# GPIO_Adapter.net
KiCad netlist of a schematic drawn in EAGLE
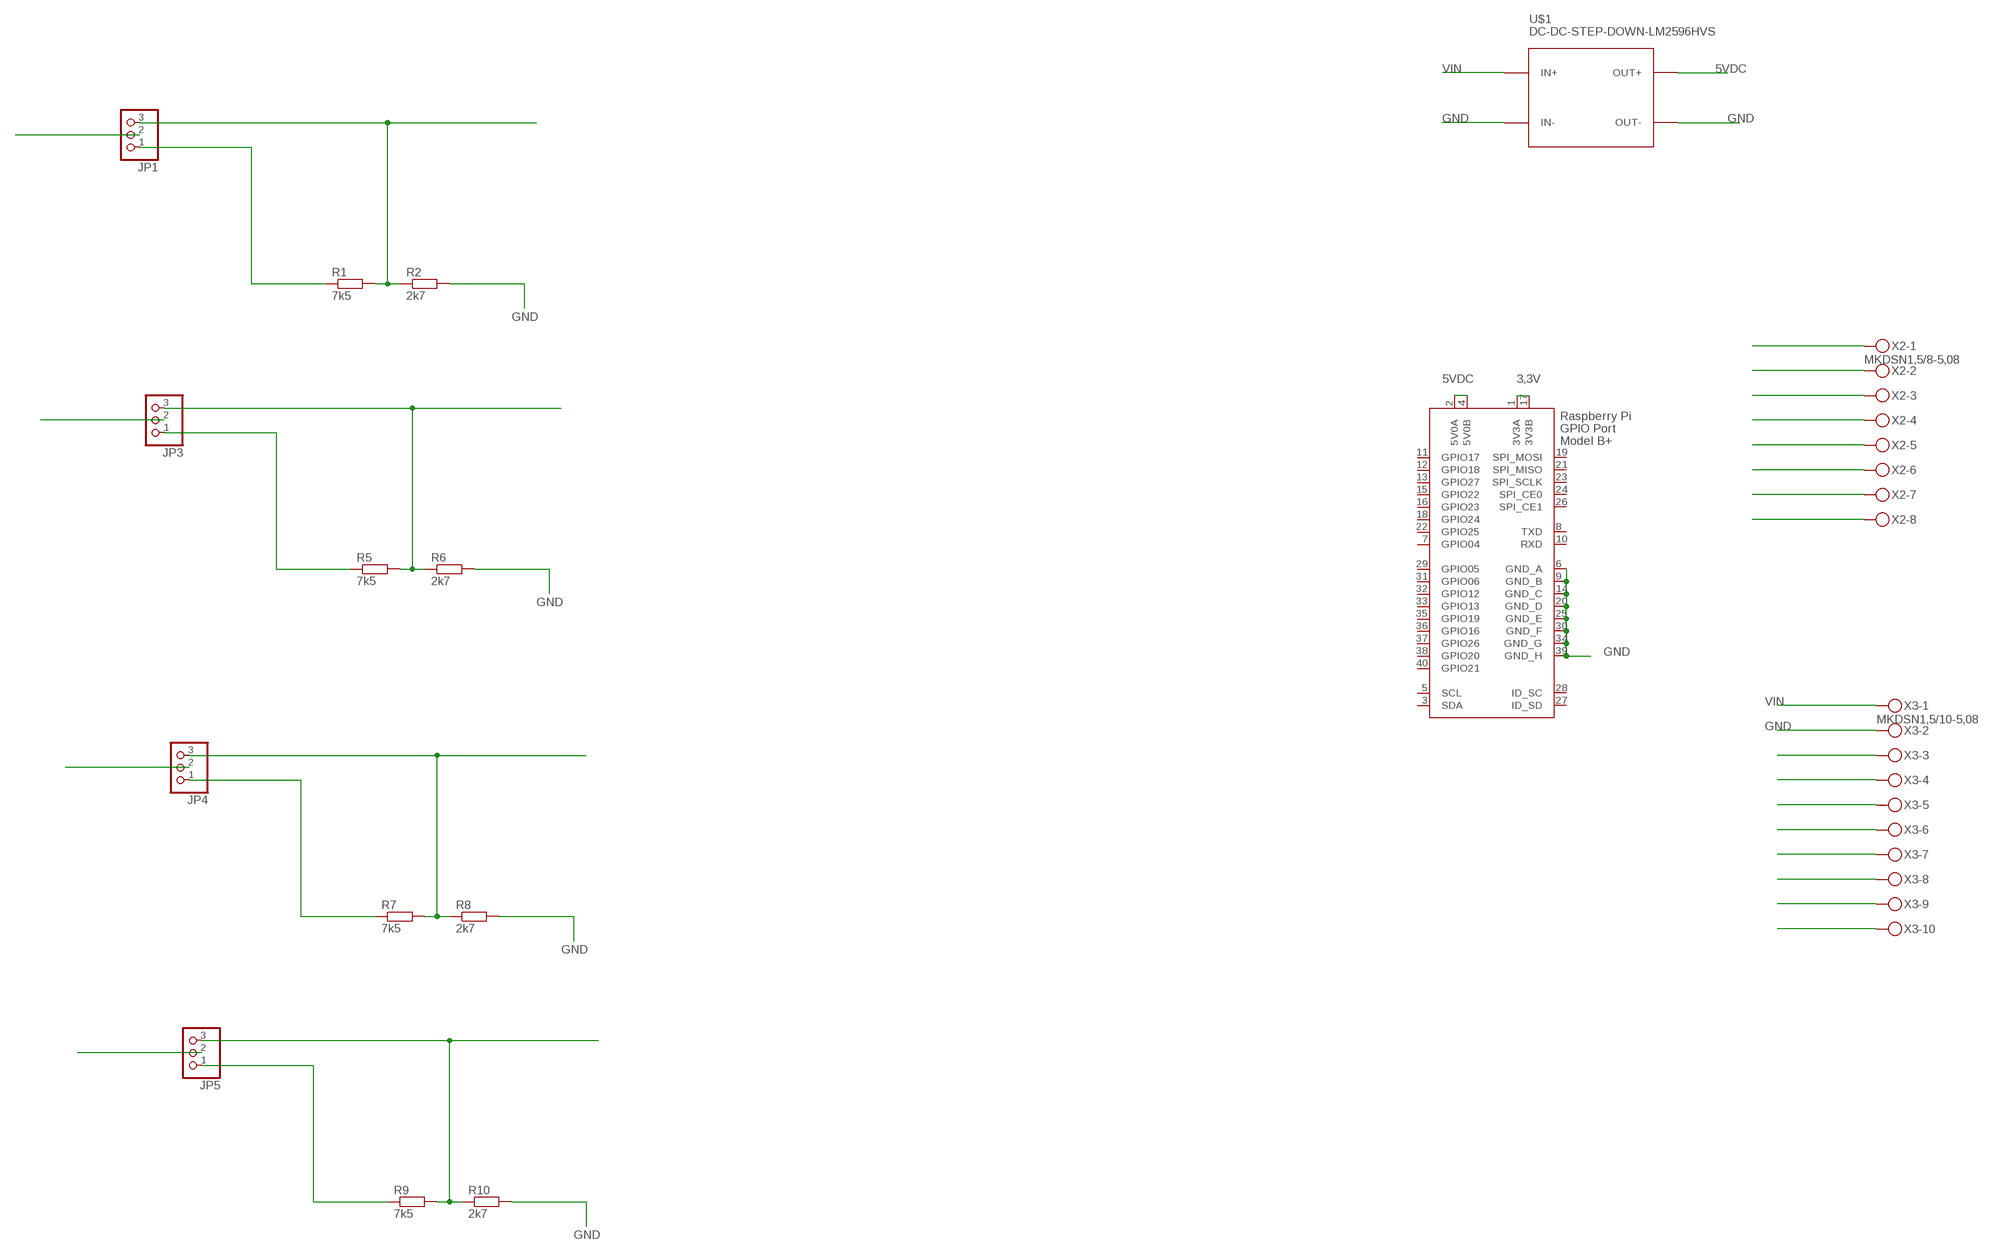
[diagram p0: schematic, sheet 1, part 1 of 3]
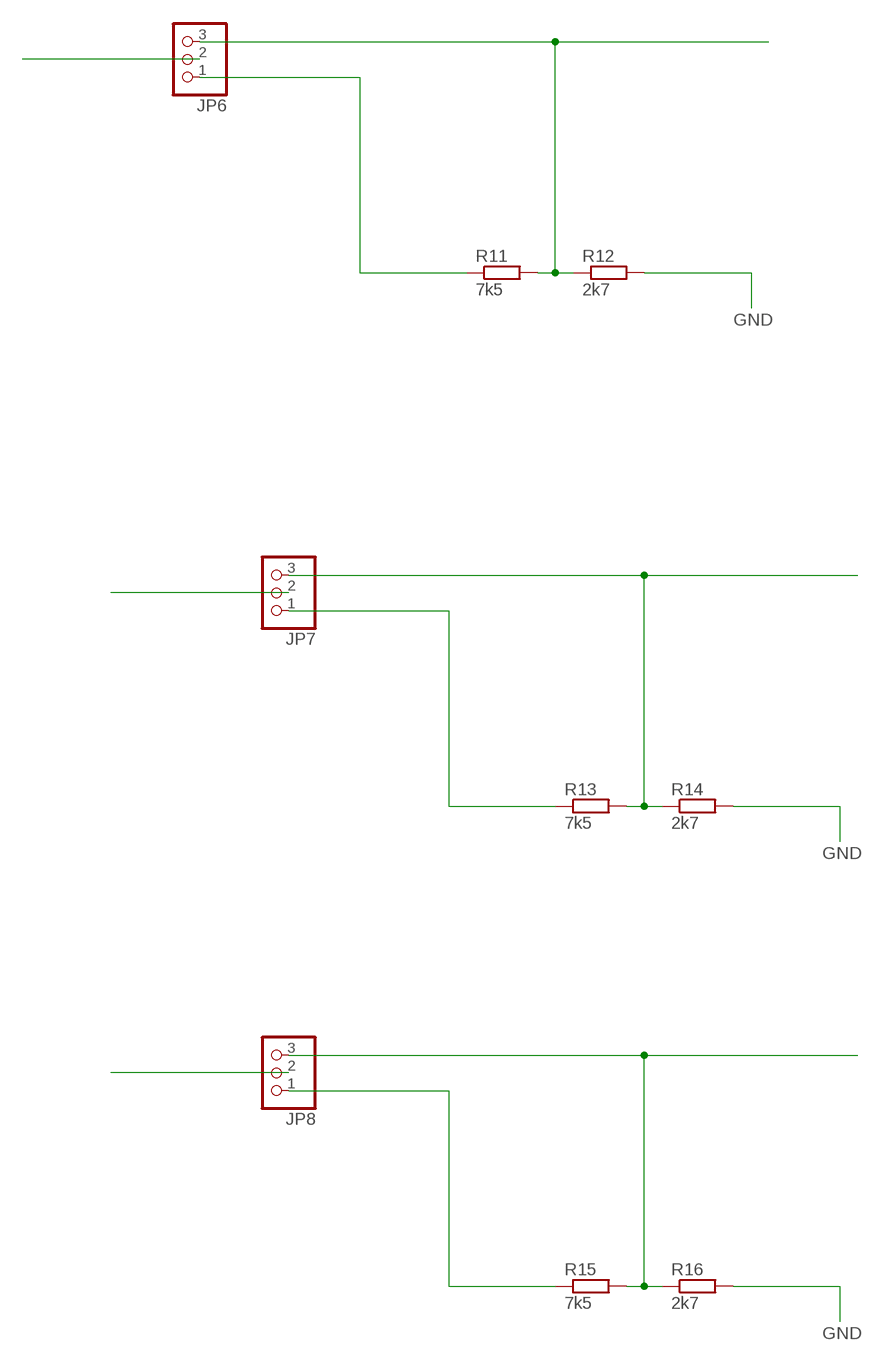
[diagram p1: schematic, sheet 1, part 2 of 3]
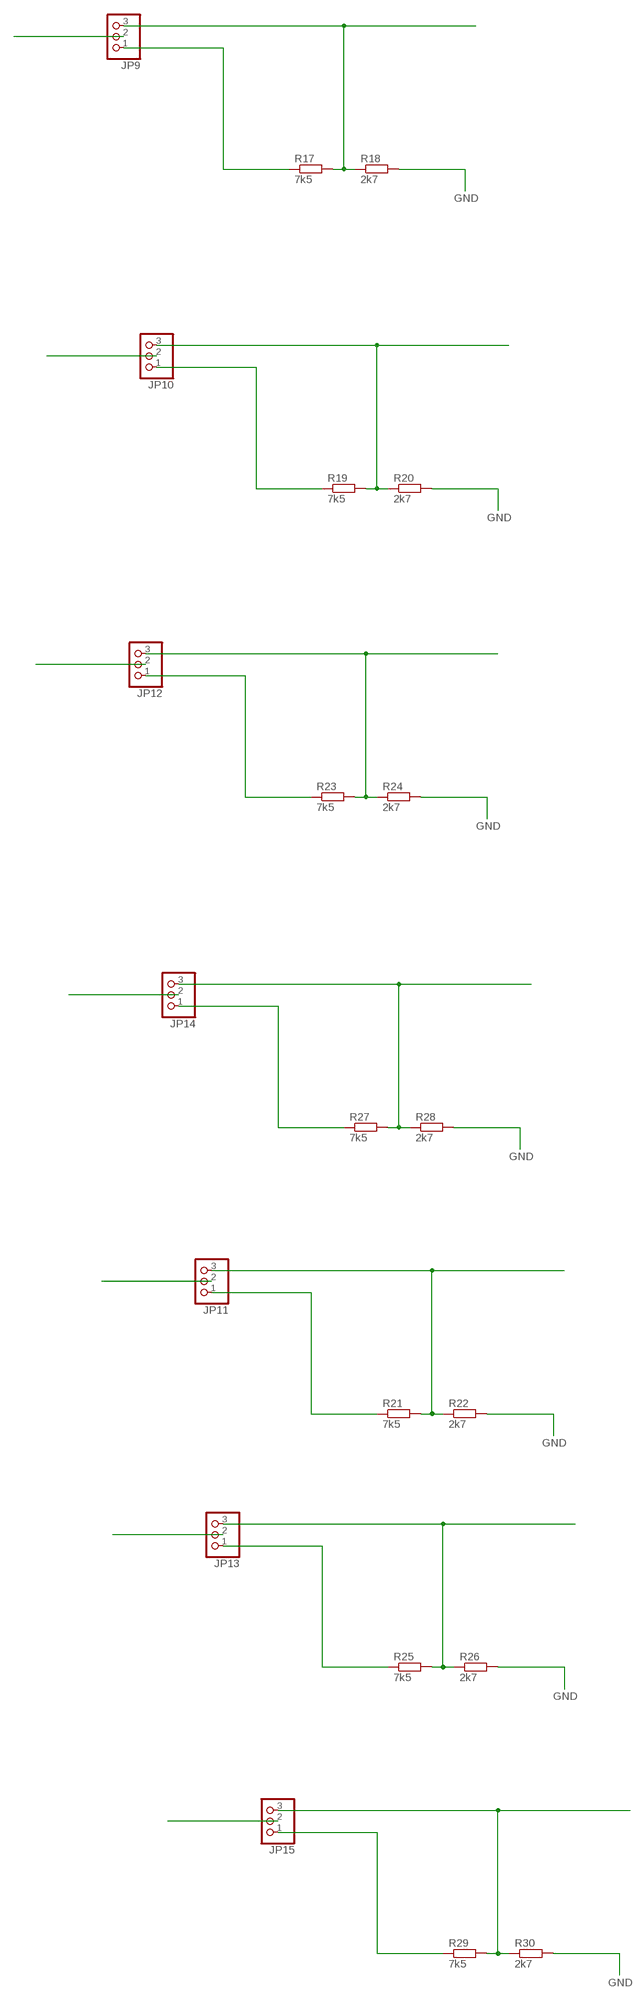
[diagram p2: schematic, sheet 1, part 3 of 3]

(export (version "E")
  (design (tool "Eeschema 10.0.6"))
  (components
    (comp (ref "JP1")
      (value "PINHD-1X3")
      (footprint "eagle-import:1X03")
      (libsource (lib "eagle-import") (part "PINHD-1X3"))
    )
    (comp (ref "JP3")
      (value "PINHD-1X3")
      (footprint "eagle-import:1X03")
      (libsource (lib "eagle-import") (part "PINHD-1X3"))
    )
    (comp (ref "JP4")
      (value "PINHD-1X3")
      (footprint "eagle-import:1X03")
      (libsource (lib "eagle-import") (part "PINHD-1X3"))
    )
    (comp (ref "JP5")
      (value "PINHD-1X3")
      (footprint "eagle-import:1X03")
      (libsource (lib "eagle-import") (part "PINHD-1X3"))
    )
    (comp (ref "JP6")
      (value "PINHD-1X3")
      (footprint "eagle-import:1X03")
      (libsource (lib "eagle-import") (part "PINHD-1X3"))
    )
    (comp (ref "JP7")
      (value "PINHD-1X3")
      (footprint "eagle-import:1X03")
      (libsource (lib "eagle-import") (part "PINHD-1X3"))
    )
    (comp (ref "JP8")
      (value "PINHD-1X3")
      (footprint "eagle-import:1X03")
      (libsource (lib "eagle-import") (part "PINHD-1X3"))
    )
    (comp (ref "JP9")
      (value "PINHD-1X3")
      (footprint "eagle-import:1X03")
      (libsource (lib "eagle-import") (part "PINHD-1X3"))
    )
    (comp (ref "JP10")
      (value "PINHD-1X3")
      (footprint "eagle-import:1X03")
      (libsource (lib "eagle-import") (part "PINHD-1X3"))
    )
    (comp (ref "JP11")
      (value "PINHD-1X3")
      (footprint "eagle-import:1X03")
      (libsource (lib "eagle-import") (part "PINHD-1X3"))
    )
    (comp (ref "JP12")
      (value "PINHD-1X3")
      (footprint "eagle-import:1X03")
      (libsource (lib "eagle-import") (part "PINHD-1X3"))
    )
    (comp (ref "JP13")
      (value "PINHD-1X3")
      (footprint "eagle-import:1X03")
      (libsource (lib "eagle-import") (part "PINHD-1X3"))
    )
    (comp (ref "JP14")
      (value "PINHD-1X3")
      (footprint "eagle-import:1X03")
      (libsource (lib "eagle-import") (part "PINHD-1X3"))
    )
    (comp (ref "JP15")
      (value "PINHD-1X3")
      (footprint "eagle-import:1X03")
      (libsource (lib "eagle-import") (part "PINHD-1X3"))
    )
    (comp (ref "R1")
      (value "7k5")
      (footprint "eagle-import:R0805")
      (libsource (lib "eagle-import") (part "R-EU_R0805"))
    )
    (comp (ref "R2")
      (value "2k7")
      (footprint "eagle-import:R0805")
      (libsource (lib "eagle-import") (part "R-EU_R0805"))
    )
    (comp (ref "R5")
      (value "7k5")
      (footprint "eagle-import:R0805")
      (libsource (lib "eagle-import") (part "R-EU_R0805"))
    )
    (comp (ref "R6")
      (value "2k7")
      (footprint "eagle-import:R0805")
      (libsource (lib "eagle-import") (part "R-EU_R0805"))
    )
    (comp (ref "R7")
      (value "7k5")
      (footprint "eagle-import:R0805")
      (libsource (lib "eagle-import") (part "R-EU_R0805"))
    )
    (comp (ref "R8")
      (value "2k7")
      (footprint "eagle-import:R0805")
      (libsource (lib "eagle-import") (part "R-EU_R0805"))
    )
    (comp (ref "R9")
      (value "7k5")
      (footprint "eagle-import:R0805")
      (libsource (lib "eagle-import") (part "R-EU_R0805"))
    )
    (comp (ref "R10")
      (value "2k7")
      (footprint "eagle-import:R0805")
      (libsource (lib "eagle-import") (part "R-EU_R0805"))
    )
    (comp (ref "R11")
      (value "7k5")
      (footprint "eagle-import:R0805")
      (libsource (lib "eagle-import") (part "R-EU_R0805"))
    )
    (comp (ref "R12")
      (value "2k7")
      (footprint "eagle-import:R0805")
      (libsource (lib "eagle-import") (part "R-EU_R0805"))
    )
    (comp (ref "R13")
      (value "7k5")
      (footprint "eagle-import:R0805")
      (libsource (lib "eagle-import") (part "R-EU_R0805"))
    )
    (comp (ref "R14")
      (value "2k7")
      (footprint "eagle-import:R0805")
      (libsource (lib "eagle-import") (part "R-EU_R0805"))
    )
    (comp (ref "R15")
      (value "7k5")
      (footprint "eagle-import:R0805")
      (libsource (lib "eagle-import") (part "R-EU_R0805"))
    )
    (comp (ref "R16")
      (value "2k7")
      (footprint "eagle-import:R0805")
      (libsource (lib "eagle-import") (part "R-EU_R0805"))
    )
    (comp (ref "R17")
      (value "7k5")
      (footprint "eagle-import:R0805")
      (libsource (lib "eagle-import") (part "R-EU_R0805"))
    )
    (comp (ref "R18")
      (value "2k7")
      (footprint "eagle-import:R0805")
      (libsource (lib "eagle-import") (part "R-EU_R0805"))
    )
    (comp (ref "R19")
      (value "7k5")
      (footprint "eagle-import:R0805")
      (libsource (lib "eagle-import") (part "R-EU_R0805"))
    )
    (comp (ref "R20")
      (value "2k7")
      (footprint "eagle-import:R0805")
      (libsource (lib "eagle-import") (part "R-EU_R0805"))
    )
    (comp (ref "R21")
      (value "7k5")
      (footprint "eagle-import:R0805")
      (libsource (lib "eagle-import") (part "R-EU_R0805"))
    )
    (comp (ref "R22")
      (value "2k7")
      (footprint "eagle-import:R0805")
      (libsource (lib "eagle-import") (part "R-EU_R0805"))
    )
    (comp (ref "R23")
      (value "7k5")
      (footprint "eagle-import:R0805")
      (libsource (lib "eagle-import") (part "R-EU_R0805"))
    )
    (comp (ref "R24")
      (value "2k7")
      (footprint "eagle-import:R0805")
      (libsource (lib "eagle-import") (part "R-EU_R0805"))
    )
    (comp (ref "R25")
      (value "7k5")
      (footprint "eagle-import:R0805")
      (libsource (lib "eagle-import") (part "R-EU_R0805"))
    )
    (comp (ref "R26")
      (value "2k7")
      (footprint "eagle-import:R0805")
      (libsource (lib "eagle-import") (part "R-EU_R0805"))
    )
    (comp (ref "R27")
      (value "7k5")
      (footprint "eagle-import:R0805")
      (libsource (lib "eagle-import") (part "R-EU_R0805"))
    )
    (comp (ref "R28")
      (value "2k7")
      (footprint "eagle-import:R0805")
      (libsource (lib "eagle-import") (part "R-EU_R0805"))
    )
    (comp (ref "R29")
      (value "7k5")
      (footprint "eagle-import:R0805")
      (libsource (lib "eagle-import") (part "R-EU_R0805"))
    )
    (comp (ref "R30")
      (value "2k7")
      (footprint "eagle-import:R0805")
      (libsource (lib "eagle-import") (part "R-EU_R0805"))
    )
    (comp (ref "U$1")
      (value "DC-DC-STEP-DOWN-LM2596HVS")
      (footprint "eagle-import:DC-DC-STEP-DOWN-LM2596HVS")
      (libsource (lib "eagle-import") (part "DC-DC-STEP-DOWN-LM2596HVS"))
    )
    (comp (ref "X1")
      (value "RASPI_BOARD_B+#_F")
      (footprint "eagle-import:RASPI_BOARD_B+_FULL")
      (libsource (lib "eagle-import") (part "RASPI_BOARD_B+#_F"))
    )
    (comp (ref "X2")
      (value "MKDSN1,5/8-5,08")
      (footprint "eagle-import:MKDSN1,5_8-5,08")
      (libsource (lib "eagle-import") (part "MKDSN1,5/8-5,08"))
    )
    (comp (ref "X3")
      (value "MKDSN1,5/10-5,08")
      (footprint "eagle-import:MKDSN1,5_10-5,08")
      (libsource (lib "eagle-import") (part "MKDSN1,5/10-5,08"))
    )
  )
  (nets
    (net (code "1") (name "/3,3V") (class "Default")
      (node (ref "X1") (pin "1") (pinfunction "3V3A_1") (pintype "power_in"))
      (node (ref "X1") (pin "17") (pinfunction "3V3B_17") (pintype "power_in"))
    )
    (net (code "2") (name "/5VDC") (class "Default")
      (node (ref "U$1") (pin "OUT+") (pinfunction "OUT+_OUT+") (pintype "bidirectional"))
      (node (ref "X1") (pin "2") (pinfunction "5V0A_2") (pintype "power_in"))
      (node (ref "X1") (pin "4") (pinfunction "5V0B_4") (pintype "power_in"))
    )
    (net (code "3") (name "/GND") (class "Default")
      (node (ref "R10") (pin "2") (pinfunction "2_2") (pintype "passive"))
      (node (ref "R12") (pin "2") (pinfunction "2_2") (pintype "passive"))
      (node (ref "R14") (pin "2") (pinfunction "2_2") (pintype "passive"))
      (node (ref "R16") (pin "2") (pinfunction "2_2") (pintype "passive"))
      (node (ref "R18") (pin "2") (pinfunction "2_2") (pintype "passive"))
      (node (ref "R2") (pin "2") (pinfunction "2_2") (pintype "passive"))
      (node (ref "R20") (pin "2") (pinfunction "2_2") (pintype "passive"))
      (node (ref "R22") (pin "2") (pinfunction "2_2") (pintype "passive"))
      (node (ref "R24") (pin "2") (pinfunction "2_2") (pintype "passive"))
      (node (ref "R26") (pin "2") (pinfunction "2_2") (pintype "passive"))
      (node (ref "R28") (pin "2") (pinfunction "2_2") (pintype "passive"))
      (node (ref "R30") (pin "2") (pinfunction "2_2") (pintype "passive"))
      (node (ref "R6") (pin "2") (pinfunction "2_2") (pintype "passive"))
      (node (ref "R8") (pin "2") (pinfunction "2_2") (pintype "passive"))
      (node (ref "U$1") (pin "IN-") (pinfunction "IN-_IN-") (pintype "bidirectional"))
      (node (ref "U$1") (pin "OUT-") (pinfunction "OUT-_OUT-") (pintype "bidirectional"))
      (node (ref "X1") (pin "14") (pinfunction "GND_C_14") (pintype "power_in"))
      (node (ref "X1") (pin "20") (pinfunction "GND_D_20") (pintype "power_in"))
      (node (ref "X1") (pin "25") (pinfunction "GND_E_25") (pintype "power_in"))
      (node (ref "X1") (pin "30") (pinfunction "GND_F_30") (pintype "power_in"))
      (node (ref "X1") (pin "34") (pinfunction "GND_G_34") (pintype "power_in"))
      (node (ref "X1") (pin "39") (pinfunction "GND_H_39") (pintype "power_in"))
      (node (ref "X1") (pin "6") (pinfunction "GND_A_6") (pintype "power_in"))
      (node (ref "X1") (pin "9") (pinfunction "GND_B_9") (pintype "power_in"))
      (node (ref "X3") (pin "2") (pinfunction "KL_2") (pintype "passive"))
    )
    (net (code "4") (name "/VIN") (class "Default")
      (node (ref "U$1") (pin "IN+") (pinfunction "IN+_IN+") (pintype "bidirectional"))
      (node (ref "X3") (pin "1") (pinfunction "KL_1") (pintype "passive"))
    )
    (net (code "5") (name "Net-(JP1-Pad1)") (class "Default")
      (node (ref "JP1") (pin "1") (pinfunction "1_1") (pintype "passive"))
      (node (ref "R1") (pin "1") (pinfunction "1_1") (pintype "passive"))
    )
    (net (code "6") (name "Net-(JP1-Pad3)") (class "Default")
      (node (ref "JP1") (pin "3") (pinfunction "3_3") (pintype "passive"))
      (node (ref "R1") (pin "2") (pinfunction "2_2") (pintype "passive"))
      (node (ref "R2") (pin "1") (pinfunction "1_1") (pintype "passive"))
    )
    (net (code "7") (name "Net-(JP3-Pad1)") (class "Default")
      (node (ref "JP3") (pin "1") (pinfunction "1_1") (pintype "passive"))
      (node (ref "R5") (pin "1") (pinfunction "1_1") (pintype "passive"))
    )
    (net (code "8") (name "Net-(JP3-Pad3)") (class "Default")
      (node (ref "JP3") (pin "3") (pinfunction "3_3") (pintype "passive"))
      (node (ref "R5") (pin "2") (pinfunction "2_2") (pintype "passive"))
      (node (ref "R6") (pin "1") (pinfunction "1_1") (pintype "passive"))
    )
    (net (code "9") (name "Net-(JP4-Pad1)") (class "Default")
      (node (ref "JP4") (pin "1") (pinfunction "1_1") (pintype "passive"))
      (node (ref "R7") (pin "1") (pinfunction "1_1") (pintype "passive"))
    )
    (net (code "10") (name "Net-(JP4-Pad3)") (class "Default")
      (node (ref "JP4") (pin "3") (pinfunction "3_3") (pintype "passive"))
      (node (ref "R7") (pin "2") (pinfunction "2_2") (pintype "passive"))
      (node (ref "R8") (pin "1") (pinfunction "1_1") (pintype "passive"))
    )
    (net (code "11") (name "Net-(JP5-Pad1)") (class "Default")
      (node (ref "JP5") (pin "1") (pinfunction "1_1") (pintype "passive"))
      (node (ref "R9") (pin "1") (pinfunction "1_1") (pintype "passive"))
    )
    (net (code "12") (name "Net-(JP5-Pad3)") (class "Default")
      (node (ref "JP5") (pin "3") (pinfunction "3_3") (pintype "passive"))
      (node (ref "R10") (pin "1") (pinfunction "1_1") (pintype "passive"))
      (node (ref "R9") (pin "2") (pinfunction "2_2") (pintype "passive"))
    )
    (net (code "13") (name "Net-(JP6-Pad1)") (class "Default")
      (node (ref "JP6") (pin "1") (pinfunction "1_1") (pintype "passive"))
      (node (ref "R11") (pin "1") (pinfunction "1_1") (pintype "passive"))
    )
    (net (code "14") (name "Net-(JP6-Pad3)") (class "Default")
      (node (ref "JP6") (pin "3") (pinfunction "3_3") (pintype "passive"))
      (node (ref "R11") (pin "2") (pinfunction "2_2") (pintype "passive"))
      (node (ref "R12") (pin "1") (pinfunction "1_1") (pintype "passive"))
    )
    (net (code "15") (name "Net-(JP7-Pad1)") (class "Default")
      (node (ref "JP7") (pin "1") (pinfunction "1_1") (pintype "passive"))
      (node (ref "R13") (pin "1") (pinfunction "1_1") (pintype "passive"))
    )
    (net (code "16") (name "Net-(JP7-Pad3)") (class "Default")
      (node (ref "JP7") (pin "3") (pinfunction "3_3") (pintype "passive"))
      (node (ref "R13") (pin "2") (pinfunction "2_2") (pintype "passive"))
      (node (ref "R14") (pin "1") (pinfunction "1_1") (pintype "passive"))
    )
    (net (code "17") (name "Net-(JP8-Pad1)") (class "Default")
      (node (ref "JP8") (pin "1") (pinfunction "1_1") (pintype "passive"))
      (node (ref "R15") (pin "1") (pinfunction "1_1") (pintype "passive"))
    )
    (net (code "18") (name "Net-(JP8-Pad3)") (class "Default")
      (node (ref "JP8") (pin "3") (pinfunction "3_3") (pintype "passive"))
      (node (ref "R15") (pin "2") (pinfunction "2_2") (pintype "passive"))
      (node (ref "R16") (pin "1") (pinfunction "1_1") (pintype "passive"))
    )
    (net (code "19") (name "Net-(JP9-Pad1)") (class "Default")
      (node (ref "JP9") (pin "1") (pinfunction "1_1") (pintype "passive"))
      (node (ref "R17") (pin "1") (pinfunction "1_1") (pintype "passive"))
    )
    (net (code "20") (name "Net-(JP9-Pad3)") (class "Default")
      (node (ref "JP9") (pin "3") (pinfunction "3_3") (pintype "passive"))
      (node (ref "R17") (pin "2") (pinfunction "2_2") (pintype "passive"))
      (node (ref "R18") (pin "1") (pinfunction "1_1") (pintype "passive"))
    )
    (net (code "21") (name "Net-(JP10-Pad1)") (class "Default")
      (node (ref "JP10") (pin "1") (pinfunction "1_1") (pintype "passive"))
      (node (ref "R19") (pin "1") (pinfunction "1_1") (pintype "passive"))
    )
    (net (code "22") (name "Net-(JP10-Pad3)") (class "Default")
      (node (ref "JP10") (pin "3") (pinfunction "3_3") (pintype "passive"))
      (node (ref "R19") (pin "2") (pinfunction "2_2") (pintype "passive"))
      (node (ref "R20") (pin "1") (pinfunction "1_1") (pintype "passive"))
    )
    (net (code "23") (name "Net-(JP11-Pad1)") (class "Default")
      (node (ref "JP11") (pin "1") (pinfunction "1_1") (pintype "passive"))
      (node (ref "R21") (pin "1") (pinfunction "1_1") (pintype "passive"))
    )
    (net (code "24") (name "Net-(JP11-Pad3)") (class "Default")
      (node (ref "JP11") (pin "3") (pinfunction "3_3") (pintype "passive"))
      (node (ref "R21") (pin "2") (pinfunction "2_2") (pintype "passive"))
      (node (ref "R22") (pin "1") (pinfunction "1_1") (pintype "passive"))
    )
    (net (code "25") (name "Net-(JP12-Pad1)") (class "Default")
      (node (ref "JP12") (pin "1") (pinfunction "1_1") (pintype "passive"))
      (node (ref "R23") (pin "1") (pinfunction "1_1") (pintype "passive"))
    )
    (net (code "26") (name "Net-(JP12-Pad3)") (class "Default")
      (node (ref "JP12") (pin "3") (pinfunction "3_3") (pintype "passive"))
      (node (ref "R23") (pin "2") (pinfunction "2_2") (pintype "passive"))
      (node (ref "R24") (pin "1") (pinfunction "1_1") (pintype "passive"))
    )
    (net (code "27") (name "Net-(JP13-Pad1)") (class "Default")
      (node (ref "JP13") (pin "1") (pinfunction "1_1") (pintype "passive"))
      (node (ref "R25") (pin "1") (pinfunction "1_1") (pintype "passive"))
    )
    (net (code "28") (name "Net-(JP13-Pad3)") (class "Default")
      (node (ref "JP13") (pin "3") (pinfunction "3_3") (pintype "passive"))
      (node (ref "R25") (pin "2") (pinfunction "2_2") (pintype "passive"))
      (node (ref "R26") (pin "1") (pinfunction "1_1") (pintype "passive"))
    )
    (net (code "29") (name "Net-(JP14-Pad1)") (class "Default")
      (node (ref "JP14") (pin "1") (pinfunction "1_1") (pintype "passive"))
      (node (ref "R27") (pin "1") (pinfunction "1_1") (pintype "passive"))
    )
    (net (code "30") (name "Net-(JP14-Pad3)") (class "Default")
      (node (ref "JP14") (pin "3") (pinfunction "3_3") (pintype "passive"))
      (node (ref "R27") (pin "2") (pinfunction "2_2") (pintype "passive"))
      (node (ref "R28") (pin "1") (pinfunction "1_1") (pintype "passive"))
    )
    (net (code "31") (name "Net-(JP15-Pad1)") (class "Default")
      (node (ref "JP15") (pin "1") (pinfunction "1_1") (pintype "passive"))
      (node (ref "R29") (pin "1") (pinfunction "1_1") (pintype "passive"))
    )
    (net (code "32") (name "Net-(JP15-Pad3)") (class "Default")
      (node (ref "JP15") (pin "3") (pinfunction "3_3") (pintype "passive"))
      (node (ref "R29") (pin "2") (pinfunction "2_2") (pintype "passive"))
      (node (ref "R30") (pin "1") (pinfunction "1_1") (pintype "passive"))
    )
    (net (code "33") (name "unconnected-(JP1-Pad2)") (class "Default")
      (node (ref "JP1") (pin "2") (pinfunction "2_2") (pintype "passive"))
    )
    (net (code "34") (name "unconnected-(JP3-Pad2)") (class "Default")
      (node (ref "JP3") (pin "2") (pinfunction "2_2") (pintype "passive"))
    )
    (net (code "35") (name "unconnected-(JP4-Pad2)") (class "Default")
      (node (ref "JP4") (pin "2") (pinfunction "2_2") (pintype "passive"))
    )
    (net (code "36") (name "unconnected-(JP5-Pad2)") (class "Default")
      (node (ref "JP5") (pin "2") (pinfunction "2_2") (pintype "passive"))
    )
    (net (code "37") (name "unconnected-(JP6-Pad2)") (class "Default")
      (node (ref "JP6") (pin "2") (pinfunction "2_2") (pintype "passive"))
    )
    (net (code "38") (name "unconnected-(JP7-Pad2)") (class "Default")
      (node (ref "JP7") (pin "2") (pinfunction "2_2") (pintype "passive"))
    )
    (net (code "39") (name "unconnected-(JP8-Pad2)") (class "Default")
      (node (ref "JP8") (pin "2") (pinfunction "2_2") (pintype "passive"))
    )
    (net (code "40") (name "unconnected-(JP9-Pad2)") (class "Default")
      (node (ref "JP9") (pin "2") (pinfunction "2_2") (pintype "passive"))
    )
    (net (code "41") (name "unconnected-(JP10-Pad2)") (class "Default")
      (node (ref "JP10") (pin "2") (pinfunction "2_2") (pintype "passive"))
    )
    (net (code "42") (name "unconnected-(JP11-Pad2)") (class "Default")
      (node (ref "JP11") (pin "2") (pinfunction "2_2") (pintype "passive"))
    )
    (net (code "43") (name "unconnected-(JP12-Pad2)") (class "Default")
      (node (ref "JP12") (pin "2") (pinfunction "2_2") (pintype "passive"))
    )
    (net (code "44") (name "unconnected-(JP13-Pad2)") (class "Default")
      (node (ref "JP13") (pin "2") (pinfunction "2_2") (pintype "passive"))
    )
    (net (code "45") (name "unconnected-(JP14-Pad2)") (class "Default")
      (node (ref "JP14") (pin "2") (pinfunction "2_2") (pintype "passive"))
    )
    (net (code "46") (name "unconnected-(JP15-Pad2)") (class "Default")
      (node (ref "JP15") (pin "2") (pinfunction "2_2") (pintype "passive"))
    )
    (net (code "47") (name "unconnected-(X1-GPIO04-Pad7)") (class "Default")
      (node (ref "X1") (pin "7") (pinfunction "GPIO04_7") (pintype "bidirectional"))
    )
    (net (code "48") (name "unconnected-(X1-GPIO05-Pad29)") (class "Default")
      (node (ref "X1") (pin "29") (pinfunction "GPIO05_29") (pintype "no_connect"))
    )
    (net (code "49") (name "unconnected-(X1-GPIO06-Pad31)") (class "Default")
      (node (ref "X1") (pin "31") (pinfunction "GPIO06_31") (pintype "no_connect"))
    )
    (net (code "50") (name "unconnected-(X1-GPIO12-Pad32)") (class "Default")
      (node (ref "X1") (pin "32") (pinfunction "GPIO12_32") (pintype "no_connect"))
    )
    (net (code "51") (name "unconnected-(X1-GPIO13-Pad33)") (class "Default")
      (node (ref "X1") (pin "33") (pinfunction "GPIO13_33") (pintype "no_connect"))
    )
    (net (code "52") (name "unconnected-(X1-GPIO16-Pad36)") (class "Default")
      (node (ref "X1") (pin "36") (pinfunction "GPIO16_36") (pintype "no_connect"))
    )
    (net (code "53") (name "unconnected-(X1-GPIO17-Pad11)") (class "Default")
      (node (ref "X1") (pin "11") (pinfunction "GPIO17_11") (pintype "bidirectional"))
    )
    (net (code "54") (name "unconnected-(X1-GPIO18-Pad12)") (class "Default")
      (node (ref "X1") (pin "12") (pinfunction "GPIO18_12") (pintype "bidirectional"))
    )
    (net (code "55") (name "unconnected-(X1-GPIO19-Pad35)") (class "Default")
      (node (ref "X1") (pin "35") (pinfunction "GPIO19_35") (pintype "no_connect"))
    )
    (net (code "56") (name "unconnected-(X1-GPIO20-Pad38)") (class "Default")
      (node (ref "X1") (pin "38") (pinfunction "GPIO20_38") (pintype "no_connect"))
    )
    (net (code "57") (name "unconnected-(X1-GPIO21-Pad40)") (class "Default")
      (node (ref "X1") (pin "40") (pinfunction "GPIO21_40") (pintype "no_connect"))
    )
    (net (code "58") (name "unconnected-(X1-GPIO22-Pad15)") (class "Default")
      (node (ref "X1") (pin "15") (pinfunction "GPIO22_15") (pintype "bidirectional"))
    )
    (net (code "59") (name "unconnected-(X1-GPIO23-Pad16)") (class "Default")
      (node (ref "X1") (pin "16") (pinfunction "GPIO23_16") (pintype "bidirectional"))
    )
    (net (code "60") (name "unconnected-(X1-GPIO24-Pad18)") (class "Default")
      (node (ref "X1") (pin "18") (pinfunction "GPIO24_18") (pintype "bidirectional"))
    )
    (net (code "61") (name "unconnected-(X1-GPIO25-Pad22)") (class "Default")
      (node (ref "X1") (pin "22") (pinfunction "GPIO25_22") (pintype "bidirectional"))
    )
    (net (code "62") (name "unconnected-(X1-GPIO26-Pad37)") (class "Default")
      (node (ref "X1") (pin "37") (pinfunction "GPIO26_37") (pintype "no_connect"))
    )
    (net (code "63") (name "unconnected-(X1-GPIO27-Pad13)") (class "Default")
      (node (ref "X1") (pin "13") (pinfunction "GPIO27_13") (pintype "bidirectional"))
    )
    (net (code "64") (name "unconnected-(X1-ID_SC-Pad28)") (class "Default")
      (node (ref "X1") (pin "28") (pinfunction "ID_SC_28") (pintype "no_connect"))
    )
    (net (code "65") (name "unconnected-(X1-ID_SD-Pad27)") (class "Default")
      (node (ref "X1") (pin "27") (pinfunction "ID_SD_27") (pintype "no_connect"))
    )
    (net (code "66") (name "unconnected-(X1-RXD-Pad10)") (class "Default")
      (node (ref "X1") (pin "10") (pinfunction "RXD_10") (pintype "bidirectional"))
    )
    (net (code "67") (name "unconnected-(X1-SCL-Pad5)") (class "Default")
      (node (ref "X1") (pin "5") (pinfunction "SCL_5") (pintype "bidirectional"))
    )
    (net (code "68") (name "unconnected-(X1-SDA-Pad3)") (class "Default")
      (node (ref "X1") (pin "3") (pinfunction "SDA_3") (pintype "bidirectional"))
    )
    (net (code "69") (name "unconnected-(X1-SPI_CE0-Pad24)") (class "Default")
      (node (ref "X1") (pin "24") (pinfunction "SPI_CE0_24") (pintype "bidirectional"))
    )
    (net (code "70") (name "unconnected-(X1-SPI_CE1-Pad26)") (class "Default")
      (node (ref "X1") (pin "26") (pinfunction "SPI_CE1_26") (pintype "bidirectional"))
    )
    (net (code "71") (name "unconnected-(X1-SPI_MISO-Pad21)") (class "Default")
      (node (ref "X1") (pin "21") (pinfunction "SPI_MISO_21") (pintype "bidirectional"))
    )
    (net (code "72") (name "unconnected-(X1-SPI_MOSI-Pad19)") (class "Default")
      (node (ref "X1") (pin "19") (pinfunction "SPI_MOSI_19") (pintype "bidirectional"))
    )
    (net (code "73") (name "unconnected-(X1-SPI_SCLK-Pad23)") (class "Default")
      (node (ref "X1") (pin "23") (pinfunction "SPI_SCLK_23") (pintype "bidirectional"))
    )
    (net (code "74") (name "unconnected-(X1-TXD-Pad8)") (class "Default")
      (node (ref "X1") (pin "8") (pinfunction "TXD_8") (pintype "bidirectional"))
    )
    (net (code "75") (name "unconnected-(X2A-KL-Pad1)") (class "Default")
      (node (ref "X2") (pin "1") (pinfunction "KL_1") (pintype "passive"))
    )
    (net (code "76") (name "unconnected-(X2B-KL-Pad2)") (class "Default")
      (node (ref "X2") (pin "2") (pinfunction "KL_2") (pintype "passive"))
    )
    (net (code "77") (name "unconnected-(X2C-KL-Pad3)") (class "Default")
      (node (ref "X2") (pin "3") (pinfunction "KL_3") (pintype "passive"))
    )
    (net (code "78") (name "unconnected-(X2D-KL-Pad4)") (class "Default")
      (node (ref "X2") (pin "4") (pinfunction "KL_4") (pintype "passive"))
    )
    (net (code "79") (name "unconnected-(X2E-KL-Pad5)") (class "Default")
      (node (ref "X2") (pin "5") (pinfunction "KL_5") (pintype "passive"))
    )
    (net (code "80") (name "unconnected-(X2F-KL-Pad6)") (class "Default")
      (node (ref "X2") (pin "6") (pinfunction "KL_6") (pintype "passive"))
    )
    (net (code "81") (name "unconnected-(X2G-KL-Pad7)") (class "Default")
      (node (ref "X2") (pin "7") (pinfunction "KL_7") (pintype "passive"))
    )
    (net (code "82") (name "unconnected-(X2H-KL-Pad8)") (class "Default")
      (node (ref "X2") (pin "8") (pinfunction "KL_8") (pintype "passive"))
    )
    (net (code "83") (name "unconnected-(X3B-KL-Pad10)") (class "Default")
      (node (ref "X3") (pin "10") (pinfunction "KL_10") (pintype "passive"))
    )
    (net (code "84") (name "unconnected-(X3D-KL-Pad3)") (class "Default")
      (node (ref "X3") (pin "3") (pinfunction "KL_3") (pintype "passive"))
    )
    (net (code "85") (name "unconnected-(X3E-KL-Pad4)") (class "Default")
      (node (ref "X3") (pin "4") (pinfunction "KL_4") (pintype "passive"))
    )
    (net (code "86") (name "unconnected-(X3F-KL-Pad5)") (class "Default")
      (node (ref "X3") (pin "5") (pinfunction "KL_5") (pintype "passive"))
    )
    (net (code "87") (name "unconnected-(X3G-KL-Pad6)") (class "Default")
      (node (ref "X3") (pin "6") (pinfunction "KL_6") (pintype "passive"))
    )
    (net (code "88") (name "unconnected-(X3H-KL-Pad7)") (class "Default")
      (node (ref "X3") (pin "7") (pinfunction "KL_7") (pintype "passive"))
    )
    (net (code "89") (name "unconnected-(X3I-KL-Pad8)") (class "Default")
      (node (ref "X3") (pin "8") (pinfunction "KL_8") (pintype "passive"))
    )
    (net (code "90") (name "unconnected-(X3J-KL-Pad9)") (class "Default")
      (node (ref "X3") (pin "9") (pinfunction "KL_9") (pintype "passive"))
    )
  )
)
